# solenoid_driver_1_0.net
KiCad netlist of a schematic drawn in EAGLE
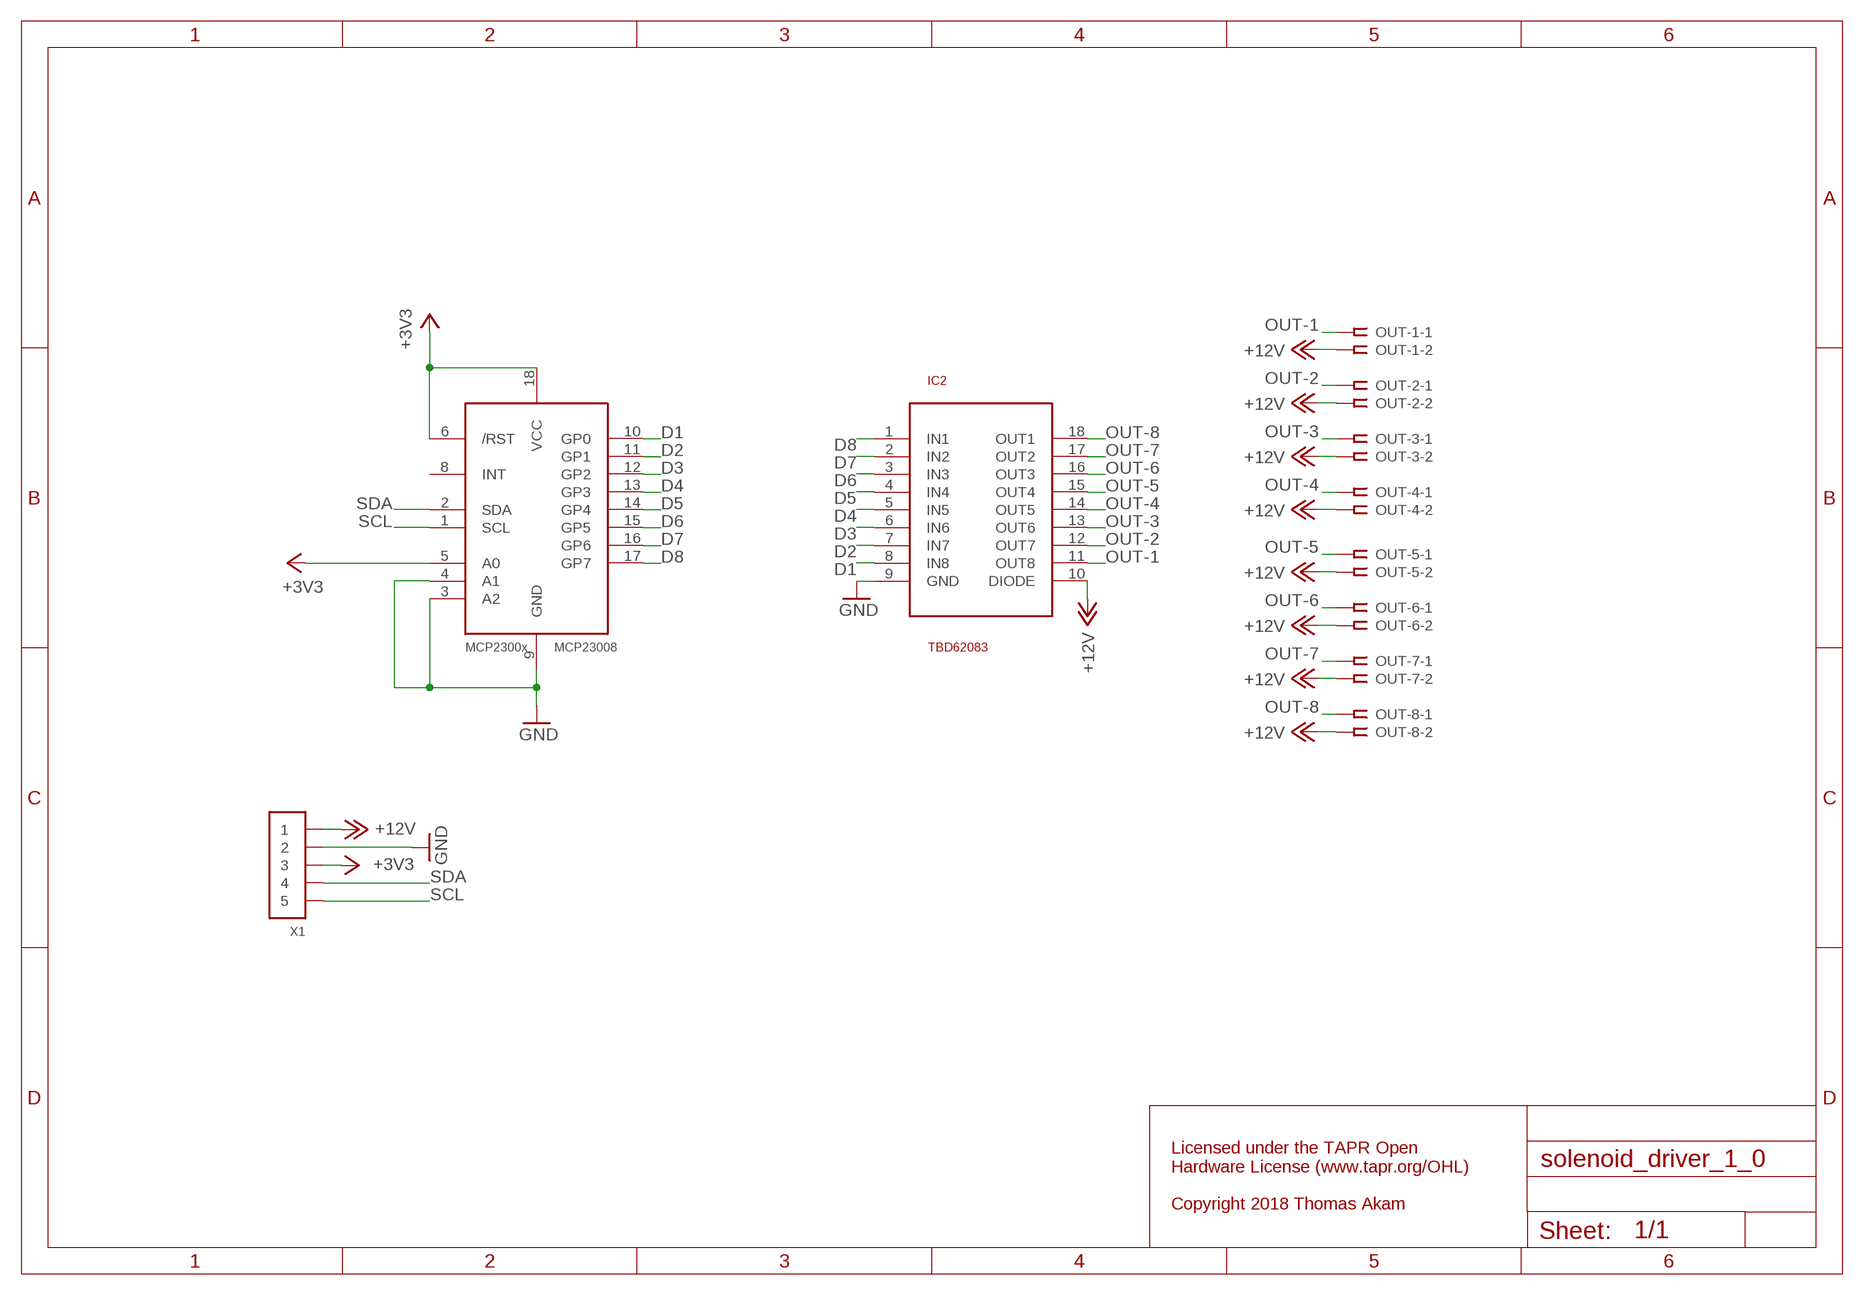
[diagram p0: schematic, sheet 1]

(export (version "E")
  (design (tool "Eeschema 10.0.6"))
  (components
    (comp (ref "IC2")
      (value "TBD62083")
      (footprint "eagle-import:SO18L")
      (libsource (lib "eagle-import") (part "ULN2803"))
    )
    (comp (ref "MCP23008")
      (value "MCP2300X/SO")
      (footprint "eagle-import:SO18W")
      (libsource (lib "eagle-import") (part "MCP2300X/SO"))
    )
    (comp (ref "OUT-1")
      (value "SSW-102-02-S-S-RA")
      (footprint "eagle-import:SSW-102-02-S-S-RA")
      (libsource (lib "eagle-import") (part "SSW-102-02-S-S-RA"))
    )
    (comp (ref "OUT-2")
      (value "SSW-102-02-S-S-RA")
      (footprint "eagle-import:SSW-102-02-S-S-RA")
      (libsource (lib "eagle-import") (part "SSW-102-02-S-S-RA"))
    )
    (comp (ref "OUT-3")
      (value "SSW-102-02-S-S-RA")
      (footprint "eagle-import:SSW-102-02-S-S-RA")
      (libsource (lib "eagle-import") (part "SSW-102-02-S-S-RA"))
    )
    (comp (ref "OUT-4")
      (value "SSW-102-02-S-S-RA")
      (footprint "eagle-import:SSW-102-02-S-S-RA")
      (libsource (lib "eagle-import") (part "SSW-102-02-S-S-RA"))
    )
    (comp (ref "OUT-5")
      (value "SSW-102-02-S-S-RA")
      (footprint "eagle-import:SSW-102-02-S-S-RA")
      (libsource (lib "eagle-import") (part "SSW-102-02-S-S-RA"))
    )
    (comp (ref "OUT-6")
      (value "SSW-102-02-S-S-RA")
      (footprint "eagle-import:SSW-102-02-S-S-RA")
      (libsource (lib "eagle-import") (part "SSW-102-02-S-S-RA"))
    )
    (comp (ref "OUT-7")
      (value "SSW-102-02-S-S-RA")
      (footprint "eagle-import:SSW-102-02-S-S-RA")
      (libsource (lib "eagle-import") (part "SSW-102-02-S-S-RA"))
    )
    (comp (ref "OUT-8")
      (value "SSW-102-02-S-S-RA")
      (footprint "eagle-import:SSW-102-02-S-S-RA")
      (libsource (lib "eagle-import") (part "SSW-102-02-S-S-RA"))
    )
    (comp (ref "X1")
      (value "CONN_5-1-53261")
      (footprint "eagle-import:PB-53261-05")
      (libsource (lib "eagle-import") (part "CONN_5-1-53261"))
    )
  )
  (nets
    (net (code "1") (name "+3V3") (class "Default")
      (node (ref "MCP23008") (pin "18") (pinfunction "VCC_18") (pintype "power_in"))
      (node (ref "MCP23008") (pin "5") (pinfunction "A0_5") (pintype "input"))
      (node (ref "MCP23008") (pin "6") (pinfunction "/RST_6") (pintype "input"))
      (node (ref "X1") (pin "3") (pinfunction "3_3") (pintype "bidirectional"))
    )
    (net (code "2") (name "+12V") (class "Default")
      (node (ref "IC2") (pin "10") (pinfunction "DIODE_10") (pintype "power_in"))
      (node (ref "OUT-1") (pin "2") (pinfunction "1_2") (pintype "passive"))
      (node (ref "OUT-2") (pin "2") (pinfunction "1_2") (pintype "passive"))
      (node (ref "OUT-3") (pin "2") (pinfunction "1_2") (pintype "passive"))
      (node (ref "OUT-4") (pin "2") (pinfunction "1_2") (pintype "passive"))
      (node (ref "OUT-5") (pin "2") (pinfunction "1_2") (pintype "passive"))
      (node (ref "OUT-6") (pin "2") (pinfunction "1_2") (pintype "passive"))
      (node (ref "OUT-7") (pin "2") (pinfunction "1_2") (pintype "passive"))
      (node (ref "OUT-8") (pin "2") (pinfunction "1_2") (pintype "passive"))
      (node (ref "X1") (pin "1") (pinfunction "1_1") (pintype "bidirectional"))
    )
    (net (code "3") (name "/D1") (class "Default")
      (node (ref "IC2") (pin "8") (pinfunction "IN8_8") (pintype "input"))
      (node (ref "MCP23008") (pin "10") (pinfunction "GP0_10") (pintype "bidirectional"))
    )
    (net (code "4") (name "/D2") (class "Default")
      (node (ref "IC2") (pin "7") (pinfunction "IN7_7") (pintype "input"))
      (node (ref "MCP23008") (pin "11") (pinfunction "GP1_11") (pintype "bidirectional"))
    )
    (net (code "5") (name "/D3") (class "Default")
      (node (ref "IC2") (pin "6") (pinfunction "IN6_6") (pintype "input"))
      (node (ref "MCP23008") (pin "12") (pinfunction "GP2_12") (pintype "bidirectional"))
    )
    (net (code "6") (name "/D4") (class "Default")
      (node (ref "IC2") (pin "5") (pinfunction "IN5_5") (pintype "input"))
      (node (ref "MCP23008") (pin "13") (pinfunction "GP3_13") (pintype "bidirectional"))
    )
    (net (code "7") (name "/D5") (class "Default")
      (node (ref "IC2") (pin "4") (pinfunction "IN4_4") (pintype "input"))
      (node (ref "MCP23008") (pin "14") (pinfunction "GP4_14") (pintype "bidirectional"))
    )
    (net (code "8") (name "/D6") (class "Default")
      (node (ref "IC2") (pin "3") (pinfunction "IN3_3") (pintype "input"))
      (node (ref "MCP23008") (pin "15") (pinfunction "GP5_15") (pintype "bidirectional"))
    )
    (net (code "9") (name "/D7") (class "Default")
      (node (ref "IC2") (pin "2") (pinfunction "IN2_2") (pintype "input"))
      (node (ref "MCP23008") (pin "16") (pinfunction "GP6_16") (pintype "bidirectional"))
    )
    (net (code "10") (name "/D8") (class "Default")
      (node (ref "IC2") (pin "1") (pinfunction "IN1_1") (pintype "input"))
      (node (ref "MCP23008") (pin "17") (pinfunction "GP7_17") (pintype "bidirectional"))
    )
    (net (code "11") (name "/OUT-1") (class "Default")
      (node (ref "IC2") (pin "11") (pinfunction "OUT8_11") (pintype "open_collector"))
      (node (ref "OUT-1") (pin "1") (pinfunction "1_1") (pintype "passive"))
    )
    (net (code "12") (name "/OUT-2") (class "Default")
      (node (ref "IC2") (pin "12") (pinfunction "OUT7_12") (pintype "open_collector"))
      (node (ref "OUT-2") (pin "1") (pinfunction "1_1") (pintype "passive"))
    )
    (net (code "13") (name "/OUT-3") (class "Default")
      (node (ref "IC2") (pin "13") (pinfunction "OUT6_13") (pintype "open_collector"))
      (node (ref "OUT-3") (pin "1") (pinfunction "1_1") (pintype "passive"))
    )
    (net (code "14") (name "/OUT-4") (class "Default")
      (node (ref "IC2") (pin "14") (pinfunction "OUT5_14") (pintype "open_collector"))
      (node (ref "OUT-4") (pin "1") (pinfunction "1_1") (pintype "passive"))
    )
    (net (code "15") (name "/OUT-5") (class "Default")
      (node (ref "IC2") (pin "15") (pinfunction "OUT4_15") (pintype "open_collector"))
      (node (ref "OUT-5") (pin "1") (pinfunction "1_1") (pintype "passive"))
    )
    (net (code "16") (name "/OUT-6") (class "Default")
      (node (ref "IC2") (pin "16") (pinfunction "OUT3_16") (pintype "open_collector"))
      (node (ref "OUT-6") (pin "1") (pinfunction "1_1") (pintype "passive"))
    )
    (net (code "17") (name "/OUT-7") (class "Default")
      (node (ref "IC2") (pin "17") (pinfunction "OUT2_17") (pintype "open_collector"))
      (node (ref "OUT-7") (pin "1") (pinfunction "1_1") (pintype "passive"))
    )
    (net (code "18") (name "/OUT-8") (class "Default")
      (node (ref "IC2") (pin "18") (pinfunction "OUT1_18") (pintype "open_collector"))
      (node (ref "OUT-8") (pin "1") (pinfunction "1_1") (pintype "passive"))
    )
    (net (code "19") (name "/SCL") (class "Default")
      (node (ref "MCP23008") (pin "1") (pinfunction "SCL_1") (pintype "bidirectional"))
      (node (ref "X1") (pin "5") (pinfunction "5_5") (pintype "bidirectional"))
    )
    (net (code "20") (name "/SDA") (class "Default")
      (node (ref "MCP23008") (pin "2") (pinfunction "SDA_2") (pintype "bidirectional"))
      (node (ref "X1") (pin "4") (pinfunction "4_4") (pintype "bidirectional"))
    )
    (net (code "21") (name "GND") (class "Default")
      (node (ref "IC2") (pin "9") (pinfunction "GND_9") (pintype "power_in"))
      (node (ref "MCP23008") (pin "3") (pinfunction "A2_3") (pintype "input"))
      (node (ref "MCP23008") (pin "4") (pinfunction "A1_4") (pintype "input"))
      (node (ref "MCP23008") (pin "9") (pinfunction "GND_9") (pintype "power_in"))
      (node (ref "X1") (pin "2") (pinfunction "2_2") (pintype "bidirectional"))
    )
    (net (code "22") (name "unconnected-(MCP23008-INT-Pad8)") (class "Default")
      (node (ref "MCP23008") (pin "8") (pinfunction "INT_8") (pintype "output"))
    )
  )
)
